# HarpTransistors.net
KiCad netlist of a schematic drawn in EAGLE
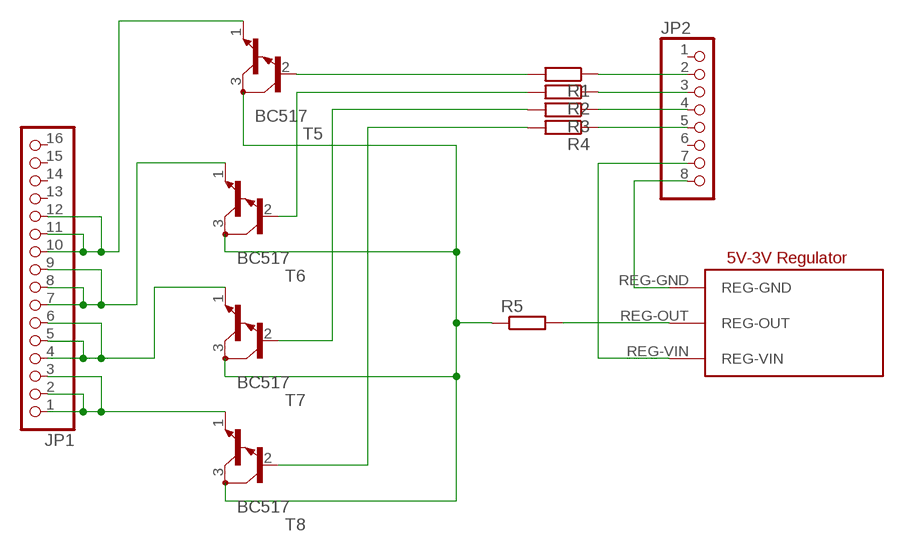
[diagram p0: schematic, sheet 1]

(export (version "E")
  (design (tool "Eeschema 10.0.6"))
  (components
    (comp (ref "JP1")
      (value "PINHD-1X16")
      (footprint "eagle-import:1X16")
      (libsource (lib "eagle-import") (part "PINHD-1X16"))
    )
    (comp (ref "JP2")
      (value "PINHD-1X8")
      (footprint "eagle-import:1X08")
      (libsource (lib "eagle-import") (part "PINHD-1X8"))
    )
    (comp (ref "R1")
      (value "R-EU_0204/5")
      (footprint "eagle-import:0204_5")
      (libsource (lib "eagle-import") (part "R-EU_0204/5"))
    )
    (comp (ref "R2")
      (value "R-EU_0204/5")
      (footprint "eagle-import:0204_5")
      (libsource (lib "eagle-import") (part "R-EU_0204/5"))
    )
    (comp (ref "R3")
      (value "R-EU_0204/5")
      (footprint "eagle-import:0204_5")
      (libsource (lib "eagle-import") (part "R-EU_0204/5"))
    )
    (comp (ref "R4")
      (value "R-EU_0204/5")
      (footprint "eagle-import:0204_5")
      (libsource (lib "eagle-import") (part "R-EU_0204/5"))
    )
    (comp (ref "R5")
      (value "R-EU_0204/5")
      (footprint "eagle-import:0204_5")
      (libsource (lib "eagle-import") (part "R-EU_0204/5"))
    )
    (comp (ref "T5")
      (value "BC517")
      (footprint "eagle-import:TO92")
      (libsource (lib "eagle-import") (part "BC517"))
    )
    (comp (ref "T6")
      (value "BC517")
      (footprint "eagle-import:TO92")
      (libsource (lib "eagle-import") (part "BC517"))
    )
    (comp (ref "T7")
      (value "BC517")
      (footprint "eagle-import:TO92")
      (libsource (lib "eagle-import") (part "BC517"))
    )
    (comp (ref "T8")
      (value "BC517")
      (footprint "eagle-import:TO92")
      (libsource (lib "eagle-import") (part "BC517"))
    )
    (comp (ref "U$1")
      (value "5V-TO-3V-REG-DEV")
      (footprint "eagle-import:5V-TO-3V-REG-PAC")
      (libsource (lib "eagle-import") (part "5V-TO-3V-REG-DEV"))
    )
  )
  (nets
    (net (code "1") (name "Net-(JP2-Pad2)") (class "Default")
      (node (ref "JP2") (pin "2") (pinfunction "2_2") (pintype "passive"))
      (node (ref "R1") (pin "1") (pinfunction "1_1") (pintype "passive"))
    )
    (net (code "2") (name "Net-(JP2-Pad3)") (class "Default")
      (node (ref "JP2") (pin "3") (pinfunction "3_3") (pintype "passive"))
      (node (ref "R2") (pin "1") (pinfunction "1_1") (pintype "passive"))
    )
    (net (code "3") (name "Net-(JP2-Pad4)") (class "Default")
      (node (ref "JP2") (pin "4") (pinfunction "4_4") (pintype "passive"))
      (node (ref "R3") (pin "1") (pinfunction "1_1") (pintype "passive"))
    )
    (net (code "4") (name "Net-(JP2-Pad5)") (class "Default")
      (node (ref "JP2") (pin "5") (pinfunction "5_5") (pintype "passive"))
      (node (ref "R4") (pin "1") (pinfunction "1_1") (pintype "passive"))
    )
    (net (code "5") (name "Net-(JP2-Pad7)") (class "Default")
      (node (ref "JP2") (pin "7") (pinfunction "7_7") (pintype "passive"))
      (node (ref "U$1") (pin "REG-VIN") (pinfunction "REG-VIN_REG-VIN") (pintype "power_in"))
    )
    (net (code "6") (name "Net-(JP2-Pad8)") (class "Default")
      (node (ref "JP2") (pin "8") (pinfunction "8_8") (pintype "passive"))
      (node (ref "U$1") (pin "REG-GND") (pinfunction "REG-GND_REG-GND") (pintype "bidirectional"))
    )
    (net (code "7") (name "Net-(R5-Pad2)") (class "Default")
      (node (ref "R5") (pin "2") (pinfunction "2_2") (pintype "passive"))
      (node (ref "U$1") (pin "REG-OUT") (pinfunction "REG-OUT_REG-OUT") (pintype "power_in"))
    )
    (net (code "8") (name "Net-(T5-B)") (class "Default")
      (node (ref "R1") (pin "2") (pinfunction "2_2") (pintype "passive"))
      (node (ref "T5") (pin "2") (pinfunction "B_2") (pintype "passive"))
    )
    (net (code "9") (name "Net-(T5-C)") (class "Default")
      (node (ref "R5") (pin "1") (pinfunction "1_1") (pintype "passive"))
      (node (ref "T5") (pin "3") (pinfunction "C_3") (pintype "passive"))
      (node (ref "T6") (pin "3") (pinfunction "C_3") (pintype "passive"))
      (node (ref "T7") (pin "3") (pinfunction "C_3") (pintype "passive"))
      (node (ref "T8") (pin "3") (pinfunction "C_3") (pintype "passive"))
    )
    (net (code "10") (name "Net-(T5-E)") (class "Default")
      (node (ref "JP1") (pin "10") (pinfunction "10_10") (pintype "passive"))
      (node (ref "JP1") (pin "11") (pinfunction "11_11") (pintype "passive"))
      (node (ref "JP1") (pin "12") (pinfunction "12_12") (pintype "passive"))
      (node (ref "T5") (pin "1") (pinfunction "E_1") (pintype "passive"))
    )
    (net (code "11") (name "Net-(T6-B)") (class "Default")
      (node (ref "R2") (pin "2") (pinfunction "2_2") (pintype "passive"))
      (node (ref "T6") (pin "2") (pinfunction "B_2") (pintype "passive"))
    )
    (net (code "12") (name "Net-(T6-E)") (class "Default")
      (node (ref "JP1") (pin "7") (pinfunction "7_7") (pintype "passive"))
      (node (ref "JP1") (pin "8") (pinfunction "8_8") (pintype "passive"))
      (node (ref "JP1") (pin "9") (pinfunction "9_9") (pintype "passive"))
      (node (ref "T6") (pin "1") (pinfunction "E_1") (pintype "passive"))
    )
    (net (code "13") (name "Net-(T7-B)") (class "Default")
      (node (ref "R3") (pin "2") (pinfunction "2_2") (pintype "passive"))
      (node (ref "T7") (pin "2") (pinfunction "B_2") (pintype "passive"))
    )
    (net (code "14") (name "Net-(T7-E)") (class "Default")
      (node (ref "JP1") (pin "4") (pinfunction "4_4") (pintype "passive"))
      (node (ref "JP1") (pin "5") (pinfunction "5_5") (pintype "passive"))
      (node (ref "JP1") (pin "6") (pinfunction "6_6") (pintype "passive"))
      (node (ref "T7") (pin "1") (pinfunction "E_1") (pintype "passive"))
    )
    (net (code "15") (name "Net-(T8-B)") (class "Default")
      (node (ref "R4") (pin "2") (pinfunction "2_2") (pintype "passive"))
      (node (ref "T8") (pin "2") (pinfunction "B_2") (pintype "passive"))
    )
    (net (code "16") (name "Net-(T8-E)") (class "Default")
      (node (ref "JP1") (pin "1") (pinfunction "1_1") (pintype "passive"))
      (node (ref "JP1") (pin "2") (pinfunction "2_2") (pintype "passive"))
      (node (ref "JP1") (pin "3") (pinfunction "3_3") (pintype "passive"))
      (node (ref "T8") (pin "1") (pinfunction "E_1") (pintype "passive"))
    )
    (net (code "17") (name "unconnected-(JP1-Pad13)") (class "Default")
      (node (ref "JP1") (pin "13") (pinfunction "13_13") (pintype "passive"))
    )
    (net (code "18") (name "unconnected-(JP1-Pad14)") (class "Default")
      (node (ref "JP1") (pin "14") (pinfunction "14_14") (pintype "passive"))
    )
    (net (code "19") (name "unconnected-(JP1-Pad15)") (class "Default")
      (node (ref "JP1") (pin "15") (pinfunction "15_15") (pintype "passive"))
    )
    (net (code "20") (name "unconnected-(JP1-Pad16)") (class "Default")
      (node (ref "JP1") (pin "16") (pinfunction "16_16") (pintype "passive"))
    )
    (net (code "21") (name "unconnected-(JP2-Pad1)") (class "Default")
      (node (ref "JP2") (pin "1") (pinfunction "1_1") (pintype "passive"))
    )
    (net (code "22") (name "unconnected-(JP2-Pad6)") (class "Default")
      (node (ref "JP2") (pin "6") (pinfunction "6_6") (pintype "passive"))
    )
  )
)
